# covid-respirator-ProtoB.net
KiCad netlist of a schematic drawn in EAGLE
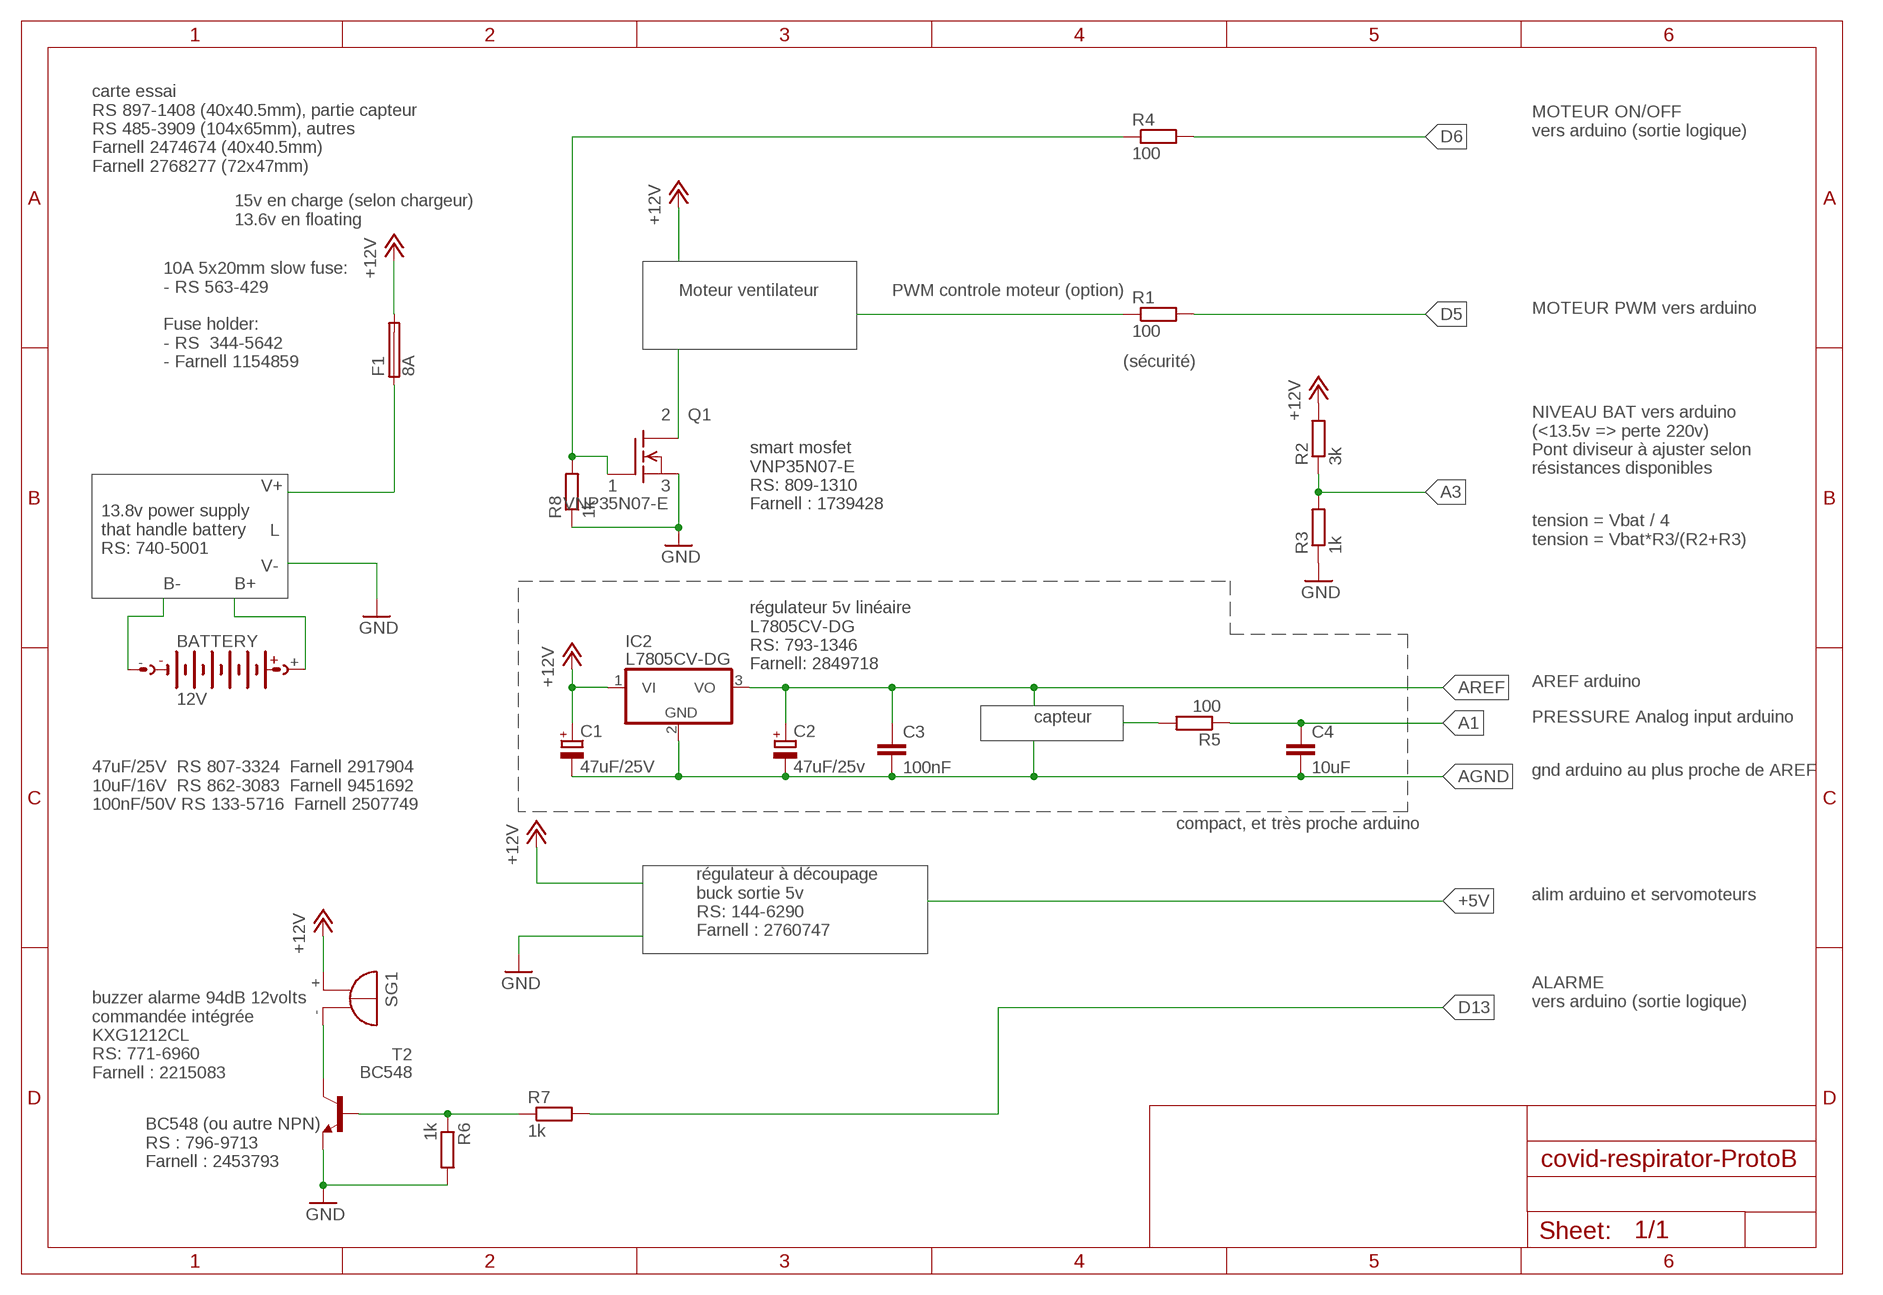
[diagram p0: schematic, sheet 1]

(export (version "E")
  (design (tool "Eeschema 10.0.6"))
  (components
    (comp (ref "BATTERY")
      (value "12V")
      (footprint "eagle-import:AB9V")
      (libsource (lib "eagle-import") (part "AB9V"))
    )
    (comp (ref "C1")
      (value "47uF/25V")
      (footprint "eagle-import:150CLZ-1010")
      (libsource (lib "eagle-import") (part "CPOL-EU150CLZ-1010"))
    )
    (comp (ref "C2")
      (value "47uF/25v")
      (footprint "eagle-import:150CLZ-1010")
      (libsource (lib "eagle-import") (part "CPOL-EU150CLZ-1010"))
    )
    (comp (ref "C3")
      (value "100nF")
      (footprint "eagle-import:C050-050X075")
      (libsource (lib "eagle-import") (part "C-EU050-050X075"))
    )
    (comp (ref "C4")
      (value "10uF")
      (footprint "eagle-import:C050-050X075")
      (libsource (lib "eagle-import") (part "C-EU050-050X075"))
    )
    (comp (ref "F1")
      (value "8A")
      (footprint "eagle-import:19560")
      (fields (field (name "MPN") "56000001009"))
      (libsource (lib "eagle-import") (part "19560"))
    )
    (comp (ref "IC2")
      (value "L7805CV-DG")
      (footprint "eagle-import:TO220H")
      (libsource (lib "eagle-import") (part "78T05"))
    )
    (comp (ref "Q1")
      (value "VNP35N07-E")
      (footprint "eagle-import:TO220")
      (libsource (lib "eagle-import") (part "BUZ72"))
    )
    (comp (ref "R1")
      (value "100")
      (footprint "eagle-import:0207_10")
      (libsource (lib "eagle-import") (part "R-EU_0207/10"))
    )
    (comp (ref "R2")
      (value "3k")
      (footprint "eagle-import:0207_10")
      (libsource (lib "eagle-import") (part "R-EU_0207/10"))
    )
    (comp (ref "R3")
      (value "1k")
      (footprint "eagle-import:0207_10")
      (libsource (lib "eagle-import") (part "R-EU_0207/10"))
    )
    (comp (ref "R4")
      (value "100")
      (footprint "eagle-import:0207_10")
      (libsource (lib "eagle-import") (part "R-EU_0207/10"))
    )
    (comp (ref "R5")
      (value "100")
      (footprint "eagle-import:0207_10")
      (libsource (lib "eagle-import") (part "R-EU_0207/10"))
    )
    (comp (ref "R6")
      (value "1k")
      (footprint "eagle-import:0207_10")
      (libsource (lib "eagle-import") (part "R-EU_0207/10"))
    )
    (comp (ref "R7")
      (value "1k")
      (footprint "eagle-import:0207_10")
      (libsource (lib "eagle-import") (part "R-EU_0207/10"))
    )
    (comp (ref "R8")
      (value "1k")
      (footprint "eagle-import:0207_10")
      (libsource (lib "eagle-import") (part "R-EU_0207/10"))
    )
    (comp (ref "SG1")
      (value "F/EB20P")
      (footprint "eagle-import:F_EB20P")
      (libsource (lib "eagle-import") (part "F/EB20P"))
    )
    (comp (ref "T2")
      (value "BC548")
      (footprint "eagle-import:TO92-CBE")
      (libsource (lib "eagle-import") (part "-NPN-TO92-CBEBC548"))
    )
  )
  (nets
    (net (code "2") (name "+12V") (class "Default")
      (node (ref "C1") (pin "+") (pinfunction "+_+") (pintype "passive"))
      (node (ref "F1") (pin "2") (pinfunction "2_2") (pintype "passive"))
      (node (ref "IC2") (pin "1") (pinfunction "VI_1") (pintype "input"))
      (node (ref "R2") (pin "2") (pinfunction "2_2") (pintype "passive"))
      (node (ref "SG1") (pin "+") (pinfunction "+_+") (pintype "passive"))
    )
    (net (code "3") (name "A1") (class "Default")
      (node (ref "C4") (pin "1") (pinfunction "1_1") (pintype "passive"))
      (node (ref "R5") (pin "1") (pinfunction "1_1") (pintype "passive"))
    )
    (net (code "4") (name "A3") (class "Default")
      (node (ref "R2") (pin "1") (pinfunction "1_1") (pintype "passive"))
      (node (ref "R3") (pin "2") (pinfunction "2_2") (pintype "passive"))
    )
    (net (code "5") (name "AGND") (class "Default")
      (node (ref "C1") (pin "-") (pinfunction "-_-") (pintype "passive"))
      (node (ref "C2") (pin "-") (pinfunction "-_-") (pintype "passive"))
      (node (ref "C3") (pin "2") (pinfunction "2_2") (pintype "passive"))
      (node (ref "C4") (pin "2") (pinfunction "2_2") (pintype "passive"))
      (node (ref "IC2") (pin "2") (pinfunction "GND_2") (pintype "passive"))
    )
    (net (code "6") (name "AREF") (class "Default")
      (node (ref "C2") (pin "+") (pinfunction "+_+") (pintype "passive"))
      (node (ref "C3") (pin "1") (pinfunction "1_1") (pintype "passive"))
      (node (ref "IC2") (pin "3") (pinfunction "VO_3") (pintype "passive"))
    )
    (net (code "7") (name "D5") (class "Default")
      (node (ref "R1") (pin "2") (pinfunction "2_2") (pintype "passive"))
    )
    (net (code "8") (name "D6") (class "Default")
      (node (ref "R4") (pin "2") (pinfunction "2_2") (pintype "passive"))
    )
    (net (code "9") (name "D13") (class "Default")
      (node (ref "R7") (pin "2") (pinfunction "2_2") (pintype "passive"))
    )
    (net (code "10") (name "GND") (class "Default")
      (node (ref "Q1") (pin "3") (pinfunction "S_3") (pintype "passive"))
      (node (ref "R3") (pin "1") (pinfunction "1_1") (pintype "passive"))
      (node (ref "R6") (pin "2") (pinfunction "2_2") (pintype "passive"))
      (node (ref "R8") (pin "1") (pinfunction "1_1") (pintype "passive"))
      (node (ref "T2") (pin "E") (pinfunction "E_E") (pintype "passive"))
    )
    (net (code "11") (name "Net-(Q1-G)") (class "Default")
      (node (ref "Q1") (pin "1") (pinfunction "G_1") (pintype "passive"))
      (node (ref "R4") (pin "1") (pinfunction "1_1") (pintype "passive"))
      (node (ref "R8") (pin "2") (pinfunction "2_2") (pintype "passive"))
    )
    (net (code "12") (name "Net-(R6-Pad1)") (class "Default")
      (node (ref "R6") (pin "1") (pinfunction "1_1") (pintype "passive"))
      (node (ref "R7") (pin "1") (pinfunction "1_1") (pintype "passive"))
      (node (ref "T2") (pin "B") (pinfunction "B_B") (pintype "passive"))
    )
    (net (code "13") (name "Net-(SG1-Pad-)") (class "Default")
      (node (ref "SG1") (pin "-") (pinfunction "-_-") (pintype "passive"))
      (node (ref "T2") (pin "C") (pinfunction "C_C") (pintype "passive"))
    )
    (net (code "14") (name "unconnected-(BATTERY-Pad+)") (class "Default")
      (node (ref "BATTERY") (pin "+") (pinfunction "+_+") (pintype "passive"))
    )
    (net (code "15") (name "unconnected-(BATTERY-Pad-)") (class "Default")
      (node (ref "BATTERY") (pin "-") (pinfunction "-_-") (pintype "passive"))
    )
    (net (code "16") (name "unconnected-(F1-Pad1)") (class "Default")
      (node (ref "F1") (pin "1") (pinfunction "1_1") (pintype "passive"))
    )
    (net (code "17") (name "unconnected-(Q1-D-Pad2)") (class "Default")
      (node (ref "Q1") (pin "2") (pinfunction "D_2") (pintype "passive"))
    )
    (net (code "18") (name "unconnected-(R1-Pad1)") (class "Default")
      (node (ref "R1") (pin "1") (pinfunction "1_1") (pintype "passive"))
    )
    (net (code "19") (name "unconnected-(R5-Pad2)") (class "Default")
      (node (ref "R5") (pin "2") (pinfunction "2_2") (pintype "passive"))
    )
  )
)
